# Power_Board_Schematic_Ver_B.net
KiCad netlist of a schematic drawn in Altium Designer
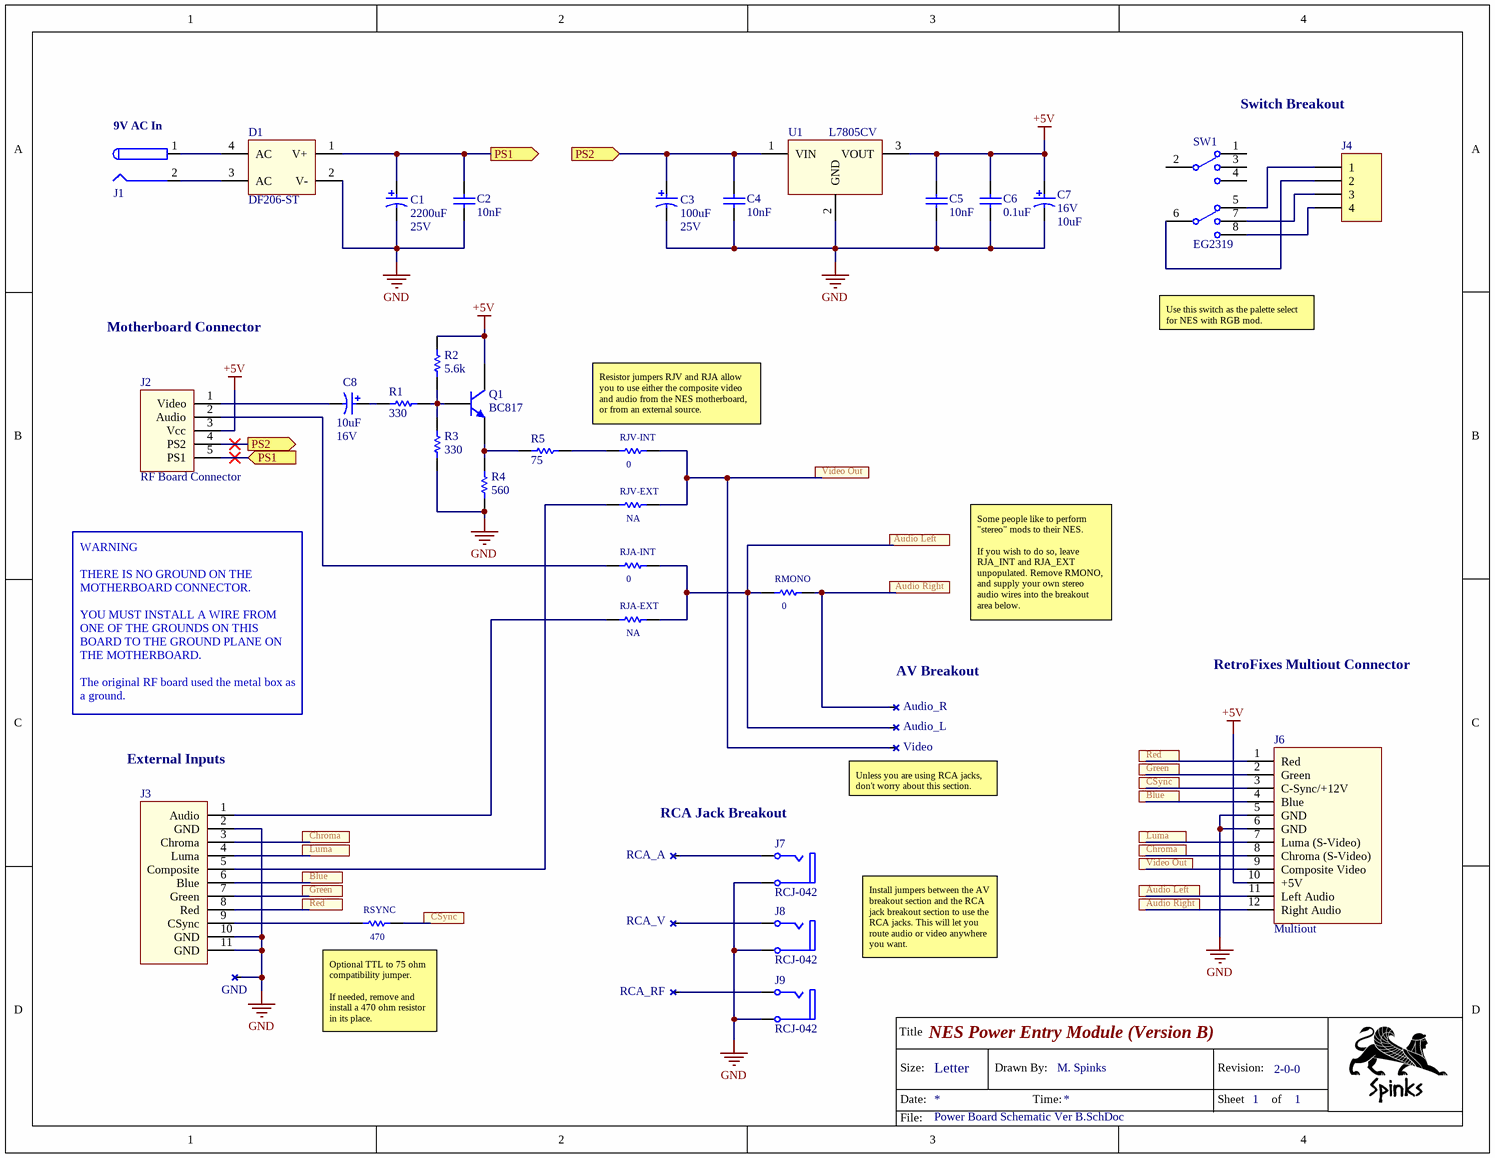
[diagram p0: Power Board Schematic Ver B.SchDoc]

(export (version "E")
  (design (tool "Eeschema 10.0.6"))
  (components
    (comp (ref "Audio_L")
      (value "Wire Pad")
      (footprint "WIREPAD-09-15")
      (description "Wire Pad, 1 Pin, Through Hole, Vertical")
      (libsource (lib "Connectors") (part "-Wire Pad"))
    )
    (comp (ref "Audio_R")
      (value "Wire Pad")
      (footprint "WIREPAD-09-15")
      (description "Wire Pad, 1 Pin, Through Hole, Vertical")
      (libsource (lib "Connectors") (part "-Wire Pad"))
    )
    (comp (ref "C1")
      (value "2200uF")
      (footprint "TH CAP-12.5X25MM-A1K2")
      (description "CAP, ALUM, TH, 12.5x25mm, 2200uF, 25V, 20%, Pitch 5.0mm")
      (fields
        (field (name "VOLTAGE") "25V")
        (field (name "REFERENCEPART") "ECA-1EHG222")
        (field (name "Comment") "Cap Aluminum")
      )
      (libsource (lib "Passive Components") (part "TH-ALUM-8-22-25V (ECA-1EHG222)"))
    )
    (comp (ref "C2")
      (value "10nF")
      (footprint "CAP 0805_N")
      (description "CAP, CER, 0805, 10nF, 50V, X7R, 10%")
      (fields (field (name "VOLTAGE") "50V") (field (name "REFERENCEPART") "VJ0603Y103KXACW1BC"))
      (libsource (lib "Passive Components") (part "0603-X7R-3-10-50V"))
    )
    (comp (ref "C3")
      (value "100uF")
      (footprint "TH CAP-6.3X11MM-A1K2")
      (description "CAP, ALUM, TH, 6.3x11mm, 100uF, 25V, 20%, Pitch 2.5mm")
      (fields
        (field (name "VOLTAGE") "25V")
        (field (name "REFERENCEPART") "ECA-1EM101")
        (field (name "Comment") "Cap Aluminum")
      )
      (libsource (lib "Passive Components") (part "TH-ALUM-7-10-25V (ECA-1EM101)"))
    )
    (comp (ref "C4")
      (value "10nF")
      (footprint "CAP 0805_N")
      (description "CAP, CER, 0805, 10nF, 50V, X7R, 10%")
      (fields (field (name "VOLTAGE") "50V") (field (name "REFERENCEPART") "VJ0603Y103KXACW1BC"))
      (libsource (lib "Passive Components") (part "0603-X7R-3-10-50V"))
    )
    (comp (ref "C5")
      (value "10nF")
      (footprint "CAP 0805_N")
      (description "CAP, CER, 0805, 10nF, 50V, X7R, 10%")
      (fields (field (name "VOLTAGE") "50V") (field (name "REFERENCEPART") "VJ0603Y103KXACW1BC"))
      (libsource (lib "Passive Components") (part "0603-X7R-3-10-50V"))
    )
    (comp (ref "C6")
      (value "0.1uF")
      (footprint "CAP 0805_N")
      (description "CAP, CER, 0805, 0.1uF, 50V, X7R, 10%")
      (fields (field (name "VOLTAGE") "50V") (field (name "REFERENCEPART") "VJ0805Y104KXXCW1BC"))
      (libsource (lib "Passive Components") (part "0805-X7R-4-10-50V"))
    )
    (comp (ref "C7")
      (value "10uF")
      (footprint "CAP EIA-A (3216) A1K2")
      (description "CAP, TANT,  1206, 10uF, 16V, 10%")
      (fields (field (name "VOLTAGE") "16V") (field (name "Comment") "Cap Tantalum"))
      (libsource (lib "Passive Components") (part "1206-TANT-6-10-16V (TAJA106K016RNJ)"))
    )
    (comp (ref "C8")
      (value "10uF")
      (footprint "CAP EIA-A (3216) A1K2")
      (description "CAP, TANT,  1206, 10uF, 16V, 10%")
      (fields (field (name "VOLTAGE") "16V") (field (name "Comment") "Cap Tantalum"))
      (libsource (lib "Passive Components") (part "1206-TANT-6-10-16V (TAJA106K016RNJ)"))
    )
    (comp (ref "D1")
      (value "DF206-ST")
      (footprint "DFS4")
      (description "Full Wave Diode Bridge")
      (libsource (lib "Semiconductors") (part "Bridge (DF206-ST)"))
    )
    (comp (ref "GND")
      (value "Wire Pad")
      (footprint "WIREPAD-09-15")
      (description "Wire Pad, 1 Pin, Through Hole, Vertical")
      (libsource (lib "Connectors") (part "-Wire Pad"))
    )
    (comp (ref "J1")
      (value "PJ-037A")
      (footprint "PWR-JCK-ALT (PJ-037A/B)")
      (description "2.1mm ID, DC Power Supply Connector, 2 Pin")
      (libsource (lib "Connectors") (part "PWR-JCK (PJ-037A)"))
    )
    (comp (ref "J2")
      (value "RF Board Connector")
      (footprint "RF Board Connector")
      (description "Motherboard Connector to RF/Power Module")
      (libsource (lib "Specialty Components") (part "RF Board Connector"))
    )
    (comp (ref "J3")
      (value "1.27mm Pitch")
      (footprint "RF Board Mod Inputs")
      (description "Video and audio inputs for the RF Board Mod")
      (libsource (lib "Specialty Components") (part "RF Board Mod Input Header"))
    )
    (comp (ref "J4")
      (value "Header 1x4 1.27mm")
      (footprint "HDR1X4-15MM VERT - L")
      (description "Header, 4 Pin, 1.5mm Pitch, Vertical")
      (libsource (lib "Specialty Components") (part "Header 1x4 - 1.5mm Vert"))
    )
    (comp (ref "J6")
      (value "Multiout")
      (footprint "Multiout-2")
      (description "SNES Multiout Connector")
      (libsource (lib "Specialty Components") (part "Multiout Connector"))
    )
    (comp (ref "J7")
      (value "RCJ-042")
      (footprint "RCA-JCK-1 (RCJ-042-ALT1)")
      (description "RCA Phono Jack, Right Angle")
      (libsource (lib "Connectors") (part "RCA-JCK-1 (RCJ-042)"))
    )
    (comp (ref "J8")
      (value "RCJ-042")
      (footprint "RCA-JCK-1 (RCJ-042-ALT1)")
      (description "RCA Phono Jack, Right Angle")
      (libsource (lib "Connectors") (part "RCA-JCK-1 (RCJ-042)"))
    )
    (comp (ref "J9")
      (value "RCJ-042")
      (footprint "RCA-JCK-1 (RCJ-042-ALT1)")
      (description "RCA Phono Jack, Right Angle")
      (libsource (lib "Connectors") (part "RCA-JCK-1 (RCJ-042)"))
    )
    (comp (ref "Q1")
      (value "BC817")
      (footprint "SOT23-3")
      (description "General Purpose Transistor, NPN, 3-Pin, B1E2C3")
      (fields (field (name "Comment") "Transistor NPN"))
      (libsource (lib "Semiconductors") (part "BC817 NPN"))
    )
    (comp (ref "R1")
      (value "330")
      (footprint "RES 0805_N")
      (description "RES, SMD")
      (fields (field (name "Comment") "Resistor"))
      (libsource (lib "Passive Components") (part "-Resistor"))
    )
    (comp (ref "R2")
      (value "5.6k")
      (footprint "RES 0805_N")
      (description "RES, SMD")
      (fields (field (name "Comment") "Resistor"))
      (libsource (lib "Passive Components") (part "-Resistor"))
    )
    (comp (ref "R3")
      (value "330")
      (footprint "RES 0805_N")
      (description "RES, SMD")
      (fields (field (name "Comment") "Resistor"))
      (libsource (lib "Passive Components") (part "-Resistor"))
    )
    (comp (ref "R4")
      (value "560")
      (footprint "RES 0805_N")
      (description "RES, SMD")
      (fields (field (name "Comment") "Resistor"))
      (libsource (lib "Passive Components") (part "-Resistor"))
    )
    (comp (ref "R5")
      (value "75")
      (footprint "RES 0805_N")
      (description "RES, SMD")
      (fields (field (name "Comment") "Resistor"))
      (libsource (lib "Passive Components") (part "-Resistor"))
    )
    (comp (ref "RCA_A")
      (value "Wire Pad")
      (footprint "WIREPAD-09-15")
      (description "Wire Pad, 1 Pin, Through Hole, Vertical")
      (libsource (lib "Connectors") (part "-Wire Pad"))
    )
    (comp (ref "RCA_RF")
      (value "Wire Pad")
      (footprint "WIREPAD-09-15")
      (description "Wire Pad, 1 Pin, Through Hole, Vertical")
      (libsource (lib "Connectors") (part "-Wire Pad"))
    )
    (comp (ref "RCA_V")
      (value "Wire Pad")
      (footprint "WIREPAD-09-15")
      (description "Wire Pad, 1 Pin, Through Hole, Vertical")
      (libsource (lib "Connectors") (part "-Wire Pad"))
    )
    (comp (ref "RJA-EXT")
      (value "NA")
      (footprint "RES 0805_N")
      (description "RES, SMD")
      (fields (field (name "Comment") "Resistor"))
      (libsource (lib "Passive Components") (part "-Resistor"))
    )
    (comp (ref "RJA-INT")
      (value "0")
      (footprint "RES 0805_N")
      (description "RES, SMD")
      (fields (field (name "Comment") "Resistor"))
      (libsource (lib "Passive Components") (part "-Resistor"))
    )
    (comp (ref "RJV-EXT")
      (value "NA")
      (footprint "RES 0805_N")
      (description "RES, SMD")
      (fields (field (name "Comment") "Resistor"))
      (libsource (lib "Passive Components") (part "-Resistor"))
    )
    (comp (ref "RJV-INT")
      (value "0")
      (footprint "RES 0805_N")
      (description "RES, SMD")
      (fields (field (name "Comment") "Resistor"))
      (libsource (lib "Passive Components") (part "-Resistor"))
    )
    (comp (ref "RMONO")
      (value "0")
      (footprint "RES 0805_N")
      (description "RES, SMD")
      (fields (field (name "Comment") "Resistor"))
      (libsource (lib "Passive Components") (part "-Resistor"))
    )
    (comp (ref "RSYNC")
      (value "470")
      (footprint "RES 0805_N")
      (description "RES, SMD")
      (fields (field (name "Comment") "Resistor"))
      (libsource (lib "Passive Components") (part "-Resistor"))
    )
    (comp (ref "SW1")
      (value "EG2319")
      (footprint "SW-DP3T (EG2319)")
      (description "Dual Pole, Three Throw")
      (fields (field (name "Comment") "DP3T"))
      (libsource (lib "Electromechanical") (part "SW-DP3T (EG2319)"))
    )
    (comp (ref "U1")
      (value "L7805CV")
      (footprint "TO-220AB")
      (description "Fixed 5V Regulator, 1.5A, Through Hole")
      (libsource (lib "Integrated Circuits") (part "L7805CV"))
    )
    (comp (ref "Video")
      (value "Wire Pad")
      (footprint "WIREPAD-09-15")
      (description "Wire Pad, 1 Pin, Through Hole, Vertical")
      (libsource (lib "Connectors") (part "-Wire Pad"))
    )
  )
  (nets
    (net (code "1") (name "+5V") (class "Default")
      (node (ref "C5") (pin "2") (pinfunction "2_2") (pintype "passive"))
      (node (ref "C6") (pin "2") (pinfunction "2_2") (pintype "passive"))
      (node (ref "C7") (pin "1") (pinfunction "A_1") (pintype "passive"))
      (node (ref "J2") (pin "3") (pinfunction "Vcc_3") (pintype "passive"))
      (node (ref "J6") (pin "10") (pinfunction "+5V_10") (pintype "passive"))
      (node (ref "Q1") (pin "3") (pinfunction "C_3") (pintype "passive"))
      (node (ref "R2") (pin "1") (pinfunction "1_1") (pintype "passive"))
      (node (ref "U1") (pin "3") (pinfunction "VOUT_3") (pintype "power_in"))
    )
    (net (code "2") (name "/Audio Left") (class "Default")
      (node (ref "Audio_L") (pin "1") (pinfunction "1_1") (pintype "passive"))
      (node (ref "J6") (pin "11") (pinfunction "Left_Audio_11") (pintype "passive"))
      (node (ref "RJA-EXT") (pin "1") (pinfunction "1_1") (pintype "passive"))
      (node (ref "RJA-INT") (pin "1") (pinfunction "1_1") (pintype "passive"))
      (node (ref "RMONO") (pin "2") (pinfunction "2_2") (pintype "passive"))
    )
    (net (code "3") (name "/Audio Right") (class "Default")
      (node (ref "Audio_R") (pin "1") (pinfunction "1_1") (pintype "passive"))
      (node (ref "J6") (pin "12") (pinfunction "Right_Audio_12") (pintype "passive"))
      (node (ref "RMONO") (pin "1") (pinfunction "1_1") (pintype "passive"))
    )
    (net (code "4") (name "/Blue") (class "Default")
      (node (ref "J3") (pin "6") (pinfunction "Blue_6") (pintype "passive"))
      (node (ref "J6") (pin "4") (pinfunction "Blue_4") (pintype "passive"))
    )
    (net (code "5") (name "/CSync") (class "Default")
      (node (ref "J6") (pin "3") (pinfunction "C-Sync/+12V_3") (pintype "passive"))
      (node (ref "RSYNC") (pin "1") (pinfunction "1_1") (pintype "passive"))
    )
    (net (code "6") (name "/Chroma") (class "Default")
      (node (ref "J3") (pin "3") (pinfunction "Chroma_3") (pintype "passive"))
      (node (ref "J6") (pin "8") (pinfunction "Chroma_(S-Video)_8") (pintype "passive"))
    )
    (net (code "7") (name "/Green") (class "Default")
      (node (ref "J3") (pin "7") (pinfunction "Green_7") (pintype "passive"))
      (node (ref "J6") (pin "2") (pinfunction "Green_2") (pintype "passive"))
    )
    (net (code "8") (name "/Luma") (class "Default")
      (node (ref "J3") (pin "4") (pinfunction "Luma_4") (pintype "passive"))
      (node (ref "J6") (pin "7") (pinfunction "Luma_(S-Video)_7") (pintype "passive"))
    )
    (net (code "9") (name "/PS1") (class "Default")
      (node (ref "C1") (pin "1") (pinfunction "A_1") (pintype "passive"))
      (node (ref "C2") (pin "2") (pinfunction "2_2") (pintype "passive"))
      (node (ref "D1") (pin "1") (pinfunction "V+_1") (pintype "passive"))
      (node (ref "J2") (pin "5") (pinfunction "PS1_5") (pintype "passive"))
    )
    (net (code "10") (name "/PS2") (class "Default")
      (node (ref "C3") (pin "1") (pinfunction "A_1") (pintype "passive"))
      (node (ref "C4") (pin "2") (pinfunction "2_2") (pintype "passive"))
      (node (ref "J2") (pin "4") (pinfunction "PS2_4") (pintype "passive"))
      (node (ref "U1") (pin "1") (pinfunction "VIN_1") (pintype "power_in"))
    )
    (net (code "11") (name "/Red") (class "Default")
      (node (ref "J3") (pin "8") (pinfunction "Red_8") (pintype "passive"))
      (node (ref "J6") (pin "1") (pinfunction "Red_1") (pintype "passive"))
    )
    (net (code "12") (name "/Video Out") (class "Default")
      (node (ref "J6") (pin "9") (pinfunction "Composite_Video_9") (pintype "passive"))
      (node (ref "RJV-EXT") (pin "1") (pinfunction "1_1") (pintype "passive"))
      (node (ref "RJV-INT") (pin "1") (pinfunction "1_1") (pintype "passive"))
      (node (ref "Video") (pin "1") (pinfunction "1_1") (pintype "passive"))
    )
    (net (code "13") (name "GND") (class "Default")
      (node (ref "C1") (pin "2") (pinfunction "K_2") (pintype "passive"))
      (node (ref "C2") (pin "1") (pinfunction "1_1") (pintype "passive"))
      (node (ref "C3") (pin "2") (pinfunction "K_2") (pintype "passive"))
      (node (ref "C4") (pin "1") (pinfunction "1_1") (pintype "passive"))
      (node (ref "C5") (pin "1") (pinfunction "1_1") (pintype "passive"))
      (node (ref "C6") (pin "1") (pinfunction "1_1") (pintype "passive"))
      (node (ref "C7") (pin "2") (pinfunction "K_2") (pintype "passive"))
      (node (ref "D1") (pin "2") (pinfunction "V-_2") (pintype "passive"))
      (node (ref "GND") (pin "1") (pinfunction "1_1") (pintype "passive"))
      (node (ref "J3") (pin "10") (pinfunction "GND_10") (pintype "passive"))
      (node (ref "J3") (pin "11") (pinfunction "GND_11") (pintype "passive"))
      (node (ref "J3") (pin "2") (pinfunction "GND_2") (pintype "passive"))
      (node (ref "J6") (pin "5") (pinfunction "GND_5") (pintype "passive"))
      (node (ref "J6") (pin "6") (pinfunction "GND_6") (pintype "passive"))
      (node (ref "J7") (pin "2") (pinfunction "Sleeve_2") (pintype "passive"))
      (node (ref "J8") (pin "2") (pinfunction "Sleeve_2") (pintype "passive"))
      (node (ref "J9") (pin "2") (pinfunction "Sleeve_2") (pintype "passive"))
      (node (ref "R3") (pin "2") (pinfunction "2_2") (pintype "passive"))
      (node (ref "R4") (pin "1") (pinfunction "1_1") (pintype "passive"))
      (node (ref "U1") (pin "2") (pinfunction "GND_2") (pintype "passive"))
    )
    (net (code "14") (name "Net-(C8-A)") (class "Default")
      (node (ref "C8") (pin "1") (pinfunction "A_1") (pintype "passive"))
      (node (ref "R1") (pin "2") (pinfunction "2_2") (pintype "passive"))
    )
    (net (code "15") (name "Net-(C8-K)") (class "Default")
      (node (ref "C8") (pin "2") (pinfunction "K_2") (pintype "passive"))
      (node (ref "J2") (pin "1") (pinfunction "Video_1") (pintype "passive"))
    )
    (net (code "16") (name "Net-(D1-AC-Pad3)") (class "Default")
      (node (ref "D1") (pin "3") (pinfunction "AC_3") (pintype "passive"))
      (node (ref "J1") (pin "2") (pinfunction "2_2") (pintype "power_in"))
    )
    (net (code "17") (name "Net-(D1-AC-Pad4)") (class "Default")
      (node (ref "D1") (pin "4") (pinfunction "AC_4") (pintype "passive"))
      (node (ref "J1") (pin "1") (pinfunction "1_1") (pintype "power_in"))
    )
    (net (code "18") (name "Net-(J2-Audio)") (class "Default")
      (node (ref "J2") (pin "2") (pinfunction "Audio_2") (pintype "passive"))
      (node (ref "RJA-INT") (pin "2") (pinfunction "2_2") (pintype "passive"))
    )
    (net (code "19") (name "Net-(J3-Audio)") (class "Default")
      (node (ref "J3") (pin "1") (pinfunction "Audio_1") (pintype "passive"))
      (node (ref "RJA-EXT") (pin "2") (pinfunction "2_2") (pintype "passive"))
    )
    (net (code "20") (name "Net-(J3-CSync)") (class "Default")
      (node (ref "J3") (pin "9") (pinfunction "CSync_9") (pintype "passive"))
      (node (ref "RSYNC") (pin "2") (pinfunction "2_2") (pintype "passive"))
    )
    (net (code "21") (name "Net-(J3-Composite)") (class "Default")
      (node (ref "J3") (pin "5") (pinfunction "Composite_5") (pintype "passive"))
      (node (ref "RJV-EXT") (pin "2") (pinfunction "2_2") (pintype "passive"))
    )
    (net (code "22") (name "Net-(J4-Pad1)") (class "Default")
      (node (ref "J4") (pin "1") (pinfunction "1_1") (pintype "passive"))
      (node (ref "SW1") (pin "5") (pinfunction "5_5") (pintype "passive"))
    )
    (net (code "23") (name "Net-(J4-Pad2)") (class "Default")
      (node (ref "J4") (pin "2") (pinfunction "2_2") (pintype "passive"))
      (node (ref "SW1") (pin "6") (pinfunction "6_6") (pintype "passive"))
    )
    (net (code "24") (name "Net-(J4-Pad3)") (class "Default")
      (node (ref "J4") (pin "3") (pinfunction "3_3") (pintype "passive"))
      (node (ref "SW1") (pin "7") (pinfunction "7_7") (pintype "passive"))
    )
    (net (code "25") (name "Net-(J4-Pad4)") (class "Default")
      (node (ref "J4") (pin "4") (pinfunction "4_4") (pintype "passive"))
      (node (ref "SW1") (pin "8") (pinfunction "8_8") (pintype "passive"))
    )
    (net (code "26") (name "Net-(J7-Tip)") (class "Default")
      (node (ref "J7") (pin "1") (pinfunction "Tip_1") (pintype "passive"))
      (node (ref "RCA_A") (pin "1") (pinfunction "1_1") (pintype "passive"))
    )
    (net (code "27") (name "Net-(J8-Tip)") (class "Default")
      (node (ref "J8") (pin "1") (pinfunction "Tip_1") (pintype "passive"))
      (node (ref "RCA_V") (pin "1") (pinfunction "1_1") (pintype "passive"))
    )
    (net (code "28") (name "Net-(J9-Tip)") (class "Default")
      (node (ref "J9") (pin "1") (pinfunction "Tip_1") (pintype "passive"))
      (node (ref "RCA_RF") (pin "1") (pinfunction "1_1") (pintype "passive"))
    )
    (net (code "29") (name "Net-(Q1-B)") (class "Default")
      (node (ref "Q1") (pin "1") (pinfunction "B_1") (pintype "passive"))
      (node (ref "R1") (pin "1") (pinfunction "1_1") (pintype "passive"))
      (node (ref "R2") (pin "2") (pinfunction "2_2") (pintype "passive"))
      (node (ref "R3") (pin "1") (pinfunction "1_1") (pintype "passive"))
    )
    (net (code "30") (name "Net-(Q1-E)") (class "Default")
      (node (ref "Q1") (pin "2") (pinfunction "E_2") (pintype "passive"))
      (node (ref "R4") (pin "2") (pinfunction "2_2") (pintype "passive"))
      (node (ref "R5") (pin "2") (pinfunction "2_2") (pintype "passive"))
    )
    (net (code "31") (name "Net-(R5-Pad1)") (class "Default")
      (node (ref "R5") (pin "1") (pinfunction "1_1") (pintype "passive"))
      (node (ref "RJV-INT") (pin "2") (pinfunction "2_2") (pintype "passive"))
    )
    (net (code "32") (name "unconnected-(SW1-Pad1)") (class "Default")
      (node (ref "SW1") (pin "1") (pinfunction "1_1") (pintype "passive"))
    )
    (net (code "33") (name "unconnected-(SW1-Pad2)") (class "Default")
      (node (ref "SW1") (pin "2") (pinfunction "2_2") (pintype "passive"))
    )
    (net (code "34") (name "unconnected-(SW1-Pad3)") (class "Default")
      (node (ref "SW1") (pin "3") (pinfunction "3_3") (pintype "passive"))
    )
    (net (code "35") (name "unconnected-(SW1-Pad4)") (class "Default")
      (node (ref "SW1") (pin "4") (pinfunction "4_4") (pintype "passive"))
    )
  )
)
